# MIDILOOP_Schematic.net
KiCad netlist of a schematic drawn in EAGLE
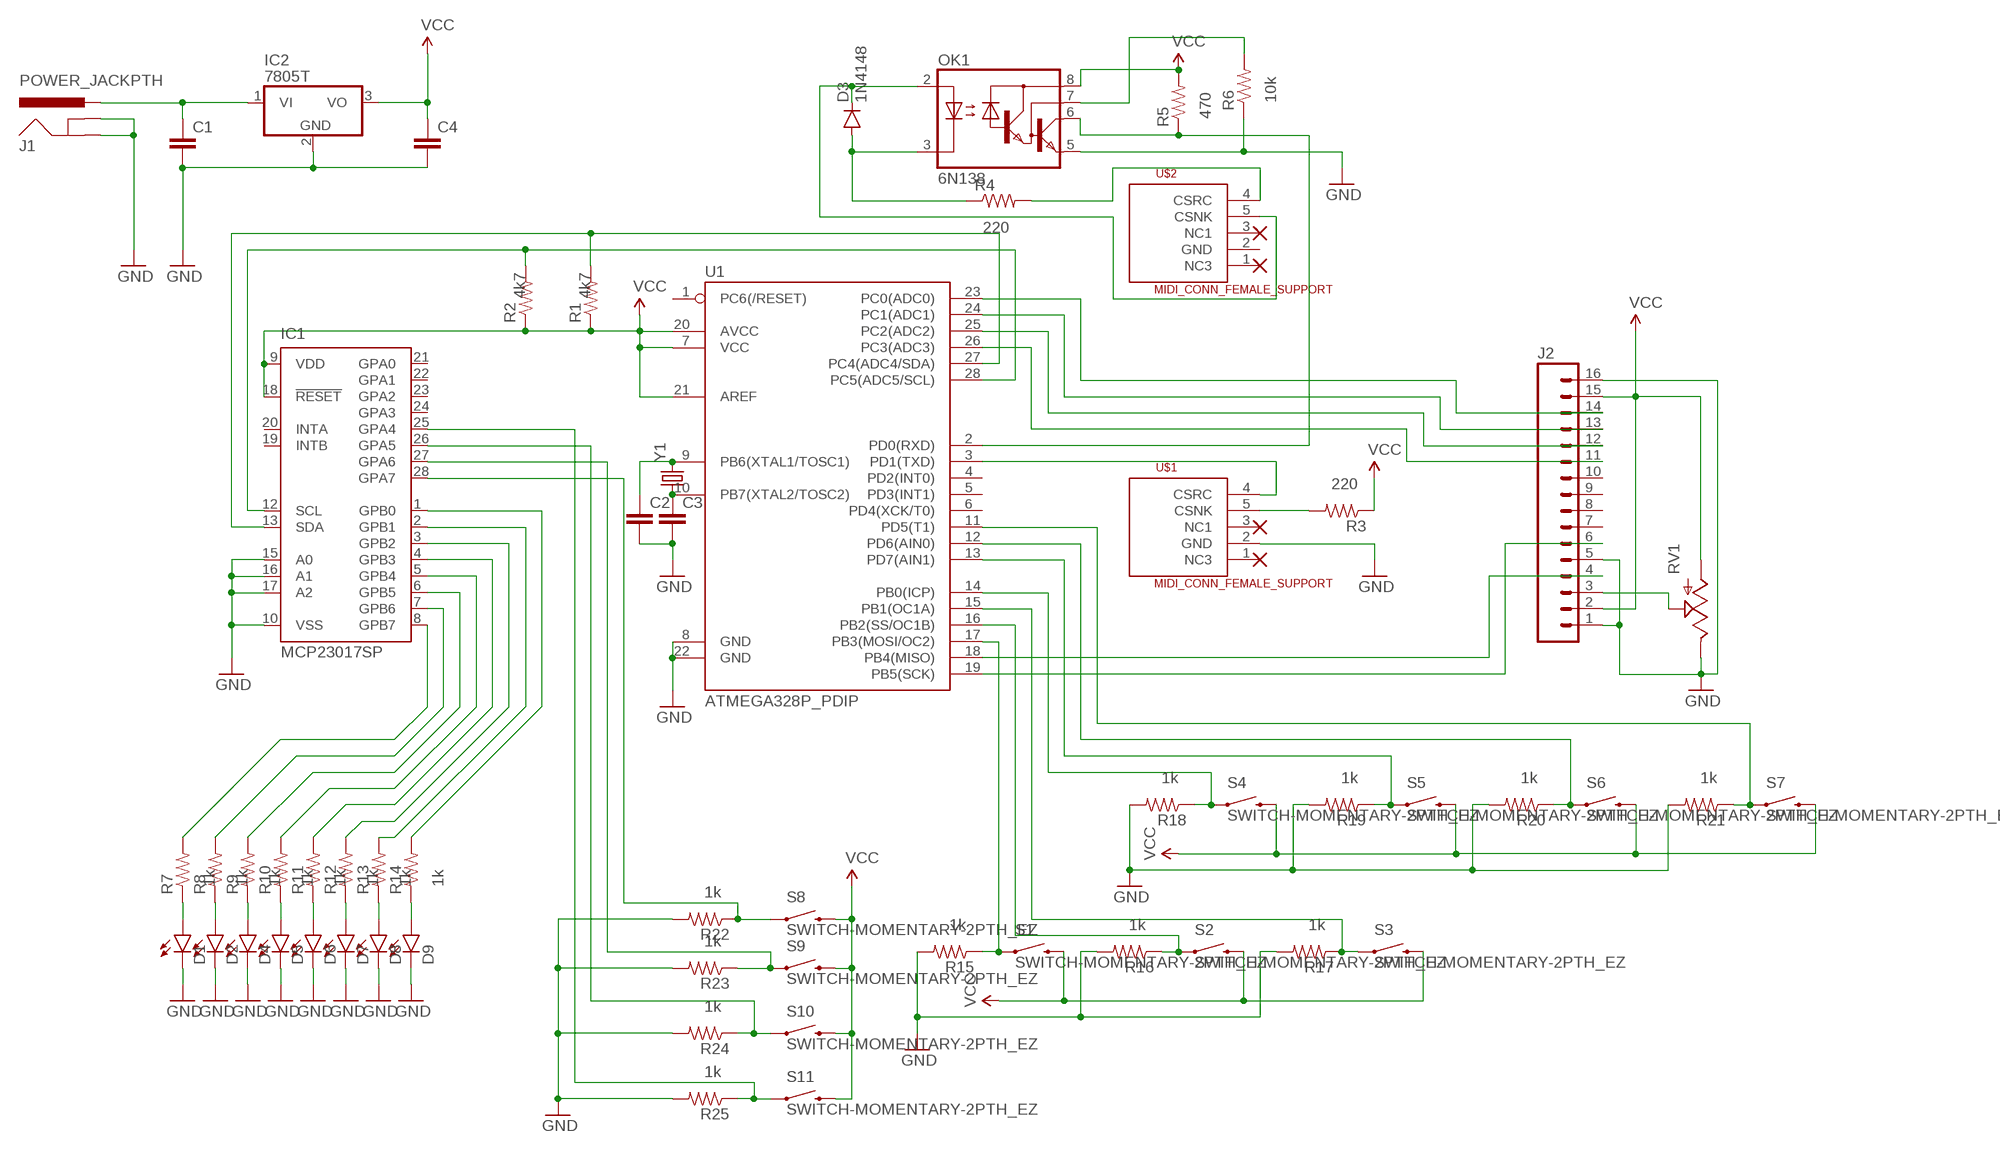
[diagram p0: schematic, sheet 1]

(export (version "E")
  (design (tool "Eeschema 10.0.6"))
  (components
    (comp (ref "C1")
      (value "CAPPTH1")
      (footprint "eagle-import:CAP-PTH-5MM")
      (libsource (lib "eagle-import") (part "SparkFun-Passives_CAPPTH1"))
    )
    (comp (ref "C2")
      (value "CAPPTH")
      (footprint "eagle-import:CAP-PTH-SMALL")
      (libsource (lib "eagle-import") (part "CAPPTH"))
    )
    (comp (ref "C3")
      (value "CAPPTH")
      (footprint "eagle-import:CAP-PTH-SMALL")
      (libsource (lib "eagle-import") (part "CAPPTH"))
    )
    (comp (ref "C4")
      (value "CAPPTH1")
      (footprint "eagle-import:CAP-PTH-5MM")
      (libsource (lib "eagle-import") (part "SparkFun-Passives_CAPPTH1"))
    )
    (comp (ref "D1")
      (value "LED3MM")
      (footprint "eagle-import:LED3MM")
      (libsource (lib "eagle-import") (part "LED3MM"))
    )
    (comp (ref "D2")
      (value "LED3MM")
      (footprint "eagle-import:LED3MM")
      (libsource (lib "eagle-import") (part "LED3MM"))
    )
    (comp (ref "D3")
      (value "1N4148")
      (footprint "eagle-import:DIODE-1N4148")
      (libsource (lib "eagle-import") (part "DIODE1N4148"))
    )
    (comp (ref "D4")
      (value "LED3MM")
      (footprint "eagle-import:LED3MM")
      (libsource (lib "eagle-import") (part "LED3MM"))
    )
    (comp (ref "D5")
      (value "LED3MM")
      (footprint "eagle-import:LED3MM")
      (libsource (lib "eagle-import") (part "LED3MM"))
    )
    (comp (ref "D6")
      (value "LED3MM")
      (footprint "eagle-import:LED3MM")
      (libsource (lib "eagle-import") (part "LED3MM"))
    )
    (comp (ref "D7")
      (value "LED3MM")
      (footprint "eagle-import:LED3MM")
      (libsource (lib "eagle-import") (part "LED3MM"))
    )
    (comp (ref "D8")
      (value "LED3MM")
      (footprint "eagle-import:LED3MM")
      (libsource (lib "eagle-import") (part "LED3MM"))
    )
    (comp (ref "D9")
      (value "LED3MM")
      (footprint "eagle-import:LED3MM")
      (libsource (lib "eagle-import") (part "LED3MM"))
    )
    (comp (ref "IC1")
      (value "MCP23017SP")
      (footprint "eagle-import:DIL28-3")
      (fields (field (name "MF") "MICROCHIP") (field (name "MPN") "MCP23017-E/SP"))
      (libsource (lib "eagle-import") (part "MCP23017SP"))
    )
    (comp (ref "IC2")
      (value "7805T")
      (footprint "eagle-import:TO220H")
      (libsource (lib "eagle-import") (part "78T05"))
    )
    (comp (ref "J1")
      (value "POWER_JACKPTH")
      (footprint "eagle-import:POWER_JACK_PTH")
      (libsource (lib "eagle-import") (part "POWER_JACKPTH"))
    )
    (comp (ref "J2")
      (value "M16LONGPADS")
      (footprint "eagle-import:1X16_LONGPADS")
      (libsource (lib "eagle-import") (part "M16LONGPADS"))
    )
    (comp (ref "OK1")
      (value "6N138")
      (footprint "eagle-import:DIL08")
      (fields (field (name "MF") "VISHAY/TELEFUNKEN"))
      (libsource (lib "eagle-import") (part "6N138"))
    )
    (comp (ref "R1")
      (value "RESISTOREZ")
      (footprint "eagle-import:AXIAL-0.3EZ")
      (fields (field (name "RESISTANCE") "4k7"))
      (libsource (lib "eagle-import") (part "RESISTOREZ"))
    )
    (comp (ref "R2")
      (value "RESISTOREZ")
      (footprint "eagle-import:AXIAL-0.3EZ")
      (fields (field (name "RESISTANCE") "4k7"))
      (libsource (lib "eagle-import") (part "RESISTOREZ"))
    )
    (comp (ref "R3")
      (value "RESISTOREZ")
      (footprint "eagle-import:AXIAL-0.3EZ")
      (fields (field (name "RESISTANCE") "220"))
      (libsource (lib "eagle-import") (part "RESISTOREZ"))
    )
    (comp (ref "R4")
      (value "RESISTOREZ")
      (footprint "eagle-import:AXIAL-0.3EZ")
      (fields (field (name "RESISTANCE") "220"))
      (libsource (lib "eagle-import") (part "RESISTOREZ"))
    )
    (comp (ref "R5")
      (value "RESISTOREZ")
      (footprint "eagle-import:AXIAL-0.3EZ")
      (fields (field (name "RESISTANCE") "470"))
      (libsource (lib "eagle-import") (part "RESISTOREZ"))
    )
    (comp (ref "R6")
      (value "RESISTOREZ")
      (footprint "eagle-import:AXIAL-0.3EZ")
      (fields (field (name "RESISTANCE") "10k"))
      (libsource (lib "eagle-import") (part "RESISTOREZ"))
    )
    (comp (ref "R7")
      (value "RESISTOREZ")
      (footprint "eagle-import:AXIAL-0.3EZ")
      (fields (field (name "RESISTANCE") "1k"))
      (libsource (lib "eagle-import") (part "RESISTOREZ"))
    )
    (comp (ref "R8")
      (value "RESISTOREZ")
      (footprint "eagle-import:AXIAL-0.3EZ")
      (fields (field (name "RESISTANCE") "1k"))
      (libsource (lib "eagle-import") (part "RESISTOREZ"))
    )
    (comp (ref "R9")
      (value "RESISTOREZ")
      (footprint "eagle-import:AXIAL-0.3EZ")
      (fields (field (name "RESISTANCE") "1k"))
      (libsource (lib "eagle-import") (part "RESISTOREZ"))
    )
    (comp (ref "R10")
      (value "RESISTOREZ")
      (footprint "eagle-import:AXIAL-0.3EZ")
      (fields (field (name "RESISTANCE") "1k"))
      (libsource (lib "eagle-import") (part "RESISTOREZ"))
    )
    (comp (ref "R11")
      (value "RESISTOREZ")
      (footprint "eagle-import:AXIAL-0.3EZ")
      (fields (field (name "RESISTANCE") "1k"))
      (libsource (lib "eagle-import") (part "RESISTOREZ"))
    )
    (comp (ref "R12")
      (value "RESISTOREZ")
      (footprint "eagle-import:AXIAL-0.3EZ")
      (fields (field (name "RESISTANCE") "1k"))
      (libsource (lib "eagle-import") (part "RESISTOREZ"))
    )
    (comp (ref "R13")
      (value "RESISTOREZ")
      (footprint "eagle-import:AXIAL-0.3EZ")
      (fields (field (name "RESISTANCE") "1k"))
      (libsource (lib "eagle-import") (part "RESISTOREZ"))
    )
    (comp (ref "R14")
      (value "RESISTOREZ")
      (footprint "eagle-import:AXIAL-0.3EZ")
      (fields (field (name "RESISTANCE") "1k"))
      (libsource (lib "eagle-import") (part "RESISTOREZ"))
    )
    (comp (ref "R15")
      (value "RESISTOREZ")
      (footprint "eagle-import:AXIAL-0.3EZ")
      (fields (field (name "RESISTANCE") "1k"))
      (libsource (lib "eagle-import") (part "RESISTOREZ"))
    )
    (comp (ref "R16")
      (value "RESISTOREZ")
      (footprint "eagle-import:AXIAL-0.3EZ")
      (fields (field (name "RESISTANCE") "1k"))
      (libsource (lib "eagle-import") (part "RESISTOREZ"))
    )
    (comp (ref "R17")
      (value "RESISTOREZ")
      (footprint "eagle-import:AXIAL-0.3EZ")
      (fields (field (name "RESISTANCE") "1k"))
      (libsource (lib "eagle-import") (part "RESISTOREZ"))
    )
    (comp (ref "R18")
      (value "RESISTOREZ")
      (footprint "eagle-import:AXIAL-0.3EZ")
      (fields (field (name "RESISTANCE") "1k"))
      (libsource (lib "eagle-import") (part "RESISTOREZ"))
    )
    (comp (ref "R19")
      (value "RESISTOREZ")
      (footprint "eagle-import:AXIAL-0.3EZ")
      (fields (field (name "RESISTANCE") "1k"))
      (libsource (lib "eagle-import") (part "RESISTOREZ"))
    )
    (comp (ref "R20")
      (value "RESISTOREZ")
      (footprint "eagle-import:AXIAL-0.3EZ")
      (fields (field (name "RESISTANCE") "1k"))
      (libsource (lib "eagle-import") (part "RESISTOREZ"))
    )
    (comp (ref "R21")
      (value "RESISTOREZ")
      (footprint "eagle-import:AXIAL-0.3EZ")
      (fields (field (name "RESISTANCE") "1k"))
      (libsource (lib "eagle-import") (part "RESISTOREZ"))
    )
    (comp (ref "R22")
      (value "RESISTOREZ")
      (footprint "eagle-import:AXIAL-0.3EZ")
      (fields (field (name "RESISTANCE") "1k"))
      (libsource (lib "eagle-import") (part "RESISTOREZ"))
    )
    (comp (ref "R23")
      (value "RESISTOREZ")
      (footprint "eagle-import:AXIAL-0.3EZ")
      (fields (field (name "RESISTANCE") "1k"))
      (libsource (lib "eagle-import") (part "RESISTOREZ"))
    )
    (comp (ref "R24")
      (value "RESISTOREZ")
      (footprint "eagle-import:AXIAL-0.3EZ")
      (fields (field (name "RESISTANCE") "1k"))
      (libsource (lib "eagle-import") (part "RESISTOREZ"))
    )
    (comp (ref "R25")
      (value "RESISTOREZ")
      (footprint "eagle-import:AXIAL-0.3EZ")
      (fields (field (name "RESISTANCE") "1k"))
      (libsource (lib "eagle-import") (part "RESISTOREZ"))
    )
    (comp (ref "RV1")
      (value "POTTRIM")
      (footprint "eagle-import:TRIM_POT")
      (libsource (lib "eagle-import") (part "POTTRIM"))
    )
    (comp (ref "S1")
      (value "SWITCH-MOMENTARY-2PTH_EZ")
      (footprint "eagle-import:TACTILE-PTH-EZ")
      (libsource (lib "eagle-import") (part "SWITCH-MOMENTARY-2PTH_EZ"))
    )
    (comp (ref "S2")
      (value "SWITCH-MOMENTARY-2PTH_EZ")
      (footprint "eagle-import:TACTILE-PTH-EZ")
      (libsource (lib "eagle-import") (part "SWITCH-MOMENTARY-2PTH_EZ"))
    )
    (comp (ref "S3")
      (value "SWITCH-MOMENTARY-2PTH_EZ")
      (footprint "eagle-import:TACTILE-PTH-EZ")
      (libsource (lib "eagle-import") (part "SWITCH-MOMENTARY-2PTH_EZ"))
    )
    (comp (ref "S4")
      (value "SWITCH-MOMENTARY-2PTH_EZ")
      (footprint "eagle-import:TACTILE-PTH-EZ")
      (libsource (lib "eagle-import") (part "SWITCH-MOMENTARY-2PTH_EZ"))
    )
    (comp (ref "S5")
      (value "SWITCH-MOMENTARY-2PTH_EZ")
      (footprint "eagle-import:TACTILE-PTH-EZ")
      (libsource (lib "eagle-import") (part "SWITCH-MOMENTARY-2PTH_EZ"))
    )
    (comp (ref "S6")
      (value "SWITCH-MOMENTARY-2PTH_EZ")
      (footprint "eagle-import:TACTILE-PTH-EZ")
      (libsource (lib "eagle-import") (part "SWITCH-MOMENTARY-2PTH_EZ"))
    )
    (comp (ref "S7")
      (value "SWITCH-MOMENTARY-2PTH_EZ")
      (footprint "eagle-import:TACTILE-PTH-EZ")
      (libsource (lib "eagle-import") (part "SWITCH-MOMENTARY-2PTH_EZ"))
    )
    (comp (ref "S8")
      (value "SWITCH-MOMENTARY-2PTH_EZ")
      (footprint "eagle-import:TACTILE-PTH-EZ")
      (libsource (lib "eagle-import") (part "SWITCH-MOMENTARY-2PTH_EZ"))
    )
    (comp (ref "S9")
      (value "SWITCH-MOMENTARY-2PTH_EZ")
      (footprint "eagle-import:TACTILE-PTH-EZ")
      (libsource (lib "eagle-import") (part "SWITCH-MOMENTARY-2PTH_EZ"))
    )
    (comp (ref "S10")
      (value "SWITCH-MOMENTARY-2PTH_EZ")
      (footprint "eagle-import:TACTILE-PTH-EZ")
      (libsource (lib "eagle-import") (part "SWITCH-MOMENTARY-2PTH_EZ"))
    )
    (comp (ref "S11")
      (value "SWITCH-MOMENTARY-2PTH_EZ")
      (footprint "eagle-import:TACTILE-PTH-EZ")
      (libsource (lib "eagle-import") (part "SWITCH-MOMENTARY-2PTH_EZ"))
    )
    (comp (ref "U$1")
      (value "MIDI_CONN_FEMALE_SUPPORT")
      (footprint "eagle-import:DIN_5_FEMALE_SUPPORT")
      (libsource (lib "eagle-import") (part "MIDI_CONN_FEMALE_SUPPORT"))
    )
    (comp (ref "U$2")
      (value "MIDI_CONN_FEMALE_SUPPORT")
      (footprint "eagle-import:DIN_5_FEMALE_SUPPORT")
      (libsource (lib "eagle-import") (part "MIDI_CONN_FEMALE_SUPPORT"))
    )
    (comp (ref "U1")
      (value "ATMEGA328P_PDIP")
      (footprint "eagle-import:DIL28-3")
      (libsource (lib "eagle-import") (part "ATMEGA328P_PDIP"))
    )
    (comp (ref "Y1")
      (value "CRYSTALHC49US")
      (footprint "eagle-import:HC49US")
      (libsource (lib "eagle-import") (part "CRYSTALHC49US"))
    )
  )
  (nets
    (net (code "1") (name "GND") (class "Default")
      (node (ref "C1") (pin "2") (pinfunction "2_2") (pintype "passive"))
      (node (ref "C2") (pin "2") (pinfunction "2_2") (pintype "passive"))
      (node (ref "C3") (pin "2") (pinfunction "2_2") (pintype "passive"))
      (node (ref "C4") (pin "2") (pinfunction "2_2") (pintype "passive"))
      (node (ref "D1") (pin "K") (pinfunction "C_K") (pintype "passive"))
      (node (ref "D2") (pin "K") (pinfunction "C_K") (pintype "passive"))
      (node (ref "D4") (pin "K") (pinfunction "C_K") (pintype "passive"))
      (node (ref "D5") (pin "K") (pinfunction "C_K") (pintype "passive"))
      (node (ref "D6") (pin "K") (pinfunction "C_K") (pintype "passive"))
      (node (ref "D7") (pin "K") (pinfunction "C_K") (pintype "passive"))
      (node (ref "D8") (pin "K") (pinfunction "C_K") (pintype "passive"))
      (node (ref "D9") (pin "K") (pinfunction "C_K") (pintype "passive"))
      (node (ref "IC1") (pin "10") (pinfunction "VSS_10") (pintype "power_in"))
      (node (ref "IC1") (pin "15") (pinfunction "A0_15") (pintype "input"))
      (node (ref "IC1") (pin "16") (pinfunction "A1_16") (pintype "input"))
      (node (ref "IC1") (pin "17") (pinfunction "A2_17") (pintype "input"))
      (node (ref "IC2") (pin "2") (pinfunction "GND_2") (pintype "passive"))
      (node (ref "J1") (pin "GND") (pinfunction "GND_GND") (pintype "bidirectional"))
      (node (ref "J1") (pin "GNDBREAK") (pinfunction "GNDBREAK_GNDBREAK") (pintype "bidirectional"))
      (node (ref "J2") (pin "1") (pinfunction "1_1") (pintype "passive"))
      (node (ref "J2") (pin "16") (pinfunction "16_16") (pintype "passive"))
      (node (ref "J2") (pin "5") (pinfunction "5_5") (pintype "passive"))
      (node (ref "OK1") (pin "5") (pinfunction "GND_5") (pintype "passive"))
      (node (ref "R15") (pin "P$2") (pinfunction "2_P$2") (pintype "passive"))
      (node (ref "R16") (pin "P$2") (pinfunction "2_P$2") (pintype "passive"))
      (node (ref "R17") (pin "P$2") (pinfunction "2_P$2") (pintype "passive"))
      (node (ref "R18") (pin "P$2") (pinfunction "2_P$2") (pintype "passive"))
      (node (ref "R19") (pin "P$2") (pinfunction "2_P$2") (pintype "passive"))
      (node (ref "R20") (pin "P$2") (pinfunction "2_P$2") (pintype "passive"))
      (node (ref "R21") (pin "P$2") (pinfunction "2_P$2") (pintype "passive"))
      (node (ref "R22") (pin "P$2") (pinfunction "2_P$2") (pintype "passive"))
      (node (ref "R23") (pin "P$2") (pinfunction "2_P$2") (pintype "passive"))
      (node (ref "R24") (pin "P$2") (pinfunction "2_P$2") (pintype "passive"))
      (node (ref "R25") (pin "P$2") (pinfunction "2_P$2") (pintype "passive"))
      (node (ref "R6") (pin "P$1") (pinfunction "1_P$1") (pintype "passive"))
      (node (ref "RV1") (pin "2") (pinfunction "E_2") (pintype "passive"))
      (node (ref "U$1") (pin "2") (pinfunction "GND_2") (pintype "bidirectional"))
      (node (ref "U1") (pin "22") (pinfunction "GND_22") (pintype "bidirectional"))
      (node (ref "U1") (pin "8") (pinfunction "GND_8") (pintype "bidirectional"))
    )
    (net (code "2") (name "Net-(IC1-GPA4)") (class "Default")
      (node (ref "IC1") (pin "25") (pinfunction "GPA4_25") (pintype "bidirectional"))
      (node (ref "R25") (pin "P$1") (pinfunction "1_P$1") (pintype "passive"))
      (node (ref "S11") (pin "1") (pinfunction "1_1") (pintype "passive"))
    )
    (net (code "3") (name "Net-(IC1-GPA5)") (class "Default")
      (node (ref "IC1") (pin "26") (pinfunction "GPA5_26") (pintype "bidirectional"))
      (node (ref "R24") (pin "P$1") (pinfunction "1_P$1") (pintype "passive"))
      (node (ref "S10") (pin "1") (pinfunction "1_1") (pintype "passive"))
    )
    (net (code "4") (name "Net-(IC1-GPA6)") (class "Default")
      (node (ref "IC1") (pin "27") (pinfunction "GPA6_27") (pintype "bidirectional"))
      (node (ref "R23") (pin "P$1") (pinfunction "1_P$1") (pintype "passive"))
      (node (ref "S9") (pin "1") (pinfunction "1_1") (pintype "passive"))
    )
    (net (code "5") (name "Net-(IC1-GPA7)") (class "Default")
      (node (ref "IC1") (pin "28") (pinfunction "GPA7_28") (pintype "bidirectional"))
      (node (ref "R22") (pin "P$1") (pinfunction "1_P$1") (pintype "passive"))
      (node (ref "S8") (pin "1") (pinfunction "1_1") (pintype "passive"))
    )
    (net (code "6") (name "Net-(IC1-GPB0)") (class "Default")
      (node (ref "IC1") (pin "1") (pinfunction "GPB0_1") (pintype "bidirectional"))
      (node (ref "R14") (pin "P$2") (pinfunction "2_P$2") (pintype "passive"))
    )
    (net (code "7") (name "Net-(IC1-GPB1)") (class "Default")
      (node (ref "IC1") (pin "2") (pinfunction "GPB1_2") (pintype "bidirectional"))
      (node (ref "R13") (pin "P$2") (pinfunction "2_P$2") (pintype "passive"))
    )
    (net (code "8") (name "Net-(IC1-GPB2)") (class "Default")
      (node (ref "IC1") (pin "3") (pinfunction "GPB2_3") (pintype "bidirectional"))
      (node (ref "R12") (pin "P$2") (pinfunction "2_P$2") (pintype "passive"))
    )
    (net (code "9") (name "Net-(IC1-GPB3)") (class "Default")
      (node (ref "IC1") (pin "4") (pinfunction "GPB3_4") (pintype "bidirectional"))
      (node (ref "R11") (pin "P$2") (pinfunction "2_P$2") (pintype "passive"))
    )
    (net (code "10") (name "Net-(IC1-GPB4)") (class "Default")
      (node (ref "IC1") (pin "5") (pinfunction "GPB4_5") (pintype "bidirectional"))
      (node (ref "R10") (pin "P$2") (pinfunction "2_P$2") (pintype "passive"))
    )
    (net (code "11") (name "Net-(IC1-GPB5)") (class "Default")
      (node (ref "IC1") (pin "6") (pinfunction "GPB5_6") (pintype "bidirectional"))
      (node (ref "R9") (pin "P$2") (pinfunction "2_P$2") (pintype "passive"))
    )
    (net (code "12") (name "Net-(IC1-GPB6)") (class "Default")
      (node (ref "IC1") (pin "7") (pinfunction "GPB6_7") (pintype "bidirectional"))
      (node (ref "R8") (pin "P$2") (pinfunction "2_P$2") (pintype "passive"))
    )
    (net (code "13") (name "Net-(IC1-GPB7)") (class "Default")
      (node (ref "IC1") (pin "8") (pinfunction "GPB7_8") (pintype "bidirectional"))
      (node (ref "R7") (pin "P$2") (pinfunction "2_P$2") (pintype "passive"))
    )
    (net (code "14") (name "Net-(IC1-SCL)") (class "Default")
      (node (ref "IC1") (pin "12") (pinfunction "SCL_12") (pintype "input"))
      (node (ref "R2") (pin "P$2") (pinfunction "2_P$2") (pintype "passive"))
      (node (ref "U1") (pin "28") (pinfunction "PC5(ADC5/SCL)_28") (pintype "bidirectional"))
    )
    (net (code "15") (name "Net-(IC1-SDA)") (class "Default")
      (node (ref "IC1") (pin "13") (pinfunction "SDA_13") (pintype "bidirectional"))
      (node (ref "R1") (pin "P$2") (pinfunction "2_P$2") (pintype "passive"))
      (node (ref "U1") (pin "27") (pinfunction "PC4(ADC4/SDA)_27") (pintype "bidirectional"))
    )
    (net (code "16") (name "Net-(IC2-VI)") (class "Default")
      (node (ref "C1") (pin "1") (pinfunction "1_1") (pintype "passive"))
      (node (ref "IC2") (pin "1") (pinfunction "VI_1") (pintype "input"))
      (node (ref "J1") (pin "PWR") (pinfunction "PWR_PWR") (pintype "bidirectional"))
    )
    (net (code "17") (name "Net-(OK1-A)") (class "Default")
      (node (ref "D3") (pin "C") (pinfunction "C_C") (pintype "passive"))
      (node (ref "OK1") (pin "2") (pinfunction "A_2") (pintype "passive"))
      (node (ref "U$2") (pin "5") (pinfunction "CSNK_5") (pintype "bidirectional"))
    )
    (net (code "18") (name "Net-(OK1-C)") (class "Default")
      (node (ref "D3") (pin "A") (pinfunction "A_A") (pintype "passive"))
      (node (ref "OK1") (pin "3") (pinfunction "C_3") (pintype "passive"))
      (node (ref "R4") (pin "P$1") (pinfunction "1_P$1") (pintype "passive"))
    )
    (net (code "19") (name "Net-(OK1-VB)") (class "Default")
      (node (ref "OK1") (pin "7") (pinfunction "VB_7") (pintype "passive"))
      (node (ref "R6") (pin "P$2") (pinfunction "2_P$2") (pintype "passive"))
    )
    (net (code "20") (name "Net-(OK1-VO)") (class "Default")
      (node (ref "OK1") (pin "6") (pinfunction "VO_6") (pintype "passive"))
      (node (ref "R5") (pin "P$1") (pinfunction "1_P$1") (pintype "passive"))
      (node (ref "U1") (pin "2") (pinfunction "PD0(RXD)_2") (pintype "bidirectional"))
    )
    (net (code "21") (name "Net-(R3-2)") (class "Default")
      (node (ref "R3") (pin "P$2") (pinfunction "2_P$2") (pintype "passive"))
      (node (ref "U$1") (pin "5") (pinfunction "CSNK_5") (pintype "bidirectional"))
    )
    (net (code "22") (name "Net-(R4-2)") (class "Default")
      (node (ref "R4") (pin "P$2") (pinfunction "2_P$2") (pintype "passive"))
      (node (ref "U$2") (pin "4") (pinfunction "CSRC_4") (pintype "bidirectional"))
    )
    (net (code "23") (name "Net-(R7-1)") (class "Default")
      (node (ref "D1") (pin "A") (pinfunction "A_A") (pintype "passive"))
      (node (ref "R7") (pin "P$1") (pinfunction "1_P$1") (pintype "passive"))
    )
    (net (code "24") (name "Net-(R8-1)") (class "Default")
      (node (ref "D2") (pin "A") (pinfunction "A_A") (pintype "passive"))
      (node (ref "R8") (pin "P$1") (pinfunction "1_P$1") (pintype "passive"))
    )
    (net (code "25") (name "Net-(R9-1)") (class "Default")
      (node (ref "D4") (pin "A") (pinfunction "A_A") (pintype "passive"))
      (node (ref "R9") (pin "P$1") (pinfunction "1_P$1") (pintype "passive"))
    )
    (net (code "26") (name "Net-(R10-1)") (class "Default")
      (node (ref "D5") (pin "A") (pinfunction "A_A") (pintype "passive"))
      (node (ref "R10") (pin "P$1") (pinfunction "1_P$1") (pintype "passive"))
    )
    (net (code "27") (name "Net-(R11-1)") (class "Default")
      (node (ref "D6") (pin "A") (pinfunction "A_A") (pintype "passive"))
      (node (ref "R11") (pin "P$1") (pinfunction "1_P$1") (pintype "passive"))
    )
    (net (code "28") (name "Net-(R12-1)") (class "Default")
      (node (ref "D7") (pin "A") (pinfunction "A_A") (pintype "passive"))
      (node (ref "R12") (pin "P$1") (pinfunction "1_P$1") (pintype "passive"))
    )
    (net (code "29") (name "Net-(R13-1)") (class "Default")
      (node (ref "D8") (pin "A") (pinfunction "A_A") (pintype "passive"))
      (node (ref "R13") (pin "P$1") (pinfunction "1_P$1") (pintype "passive"))
    )
    (net (code "30") (name "Net-(R14-1)") (class "Default")
      (node (ref "D9") (pin "A") (pinfunction "A_A") (pintype "passive"))
      (node (ref "R14") (pin "P$1") (pinfunction "1_P$1") (pintype "passive"))
    )
    (net (code "31") (name "Net-(R15-1)") (class "Default")
      (node (ref "R15") (pin "P$1") (pinfunction "1_P$1") (pintype "passive"))
      (node (ref "S1") (pin "1") (pinfunction "1_1") (pintype "passive"))
      (node (ref "U1") (pin "17") (pinfunction "PB3(MOSI/OC2)_17") (pintype "bidirectional"))
    )
    (net (code "32") (name "Net-(R16-1)") (class "Default")
      (node (ref "R16") (pin "P$1") (pinfunction "1_P$1") (pintype "passive"))
      (node (ref "S2") (pin "1") (pinfunction "1_1") (pintype "passive"))
      (node (ref "U1") (pin "16") (pinfunction "PB2(SS/OC1B)_16") (pintype "bidirectional"))
    )
    (net (code "33") (name "Net-(R17-1)") (class "Default")
      (node (ref "R17") (pin "P$1") (pinfunction "1_P$1") (pintype "passive"))
      (node (ref "S3") (pin "1") (pinfunction "1_1") (pintype "passive"))
      (node (ref "U1") (pin "15") (pinfunction "PB1(OC1A)_15") (pintype "bidirectional"))
    )
    (net (code "34") (name "Net-(R18-1)") (class "Default")
      (node (ref "R18") (pin "P$1") (pinfunction "1_P$1") (pintype "passive"))
      (node (ref "S4") (pin "1") (pinfunction "1_1") (pintype "passive"))
      (node (ref "U1") (pin "14") (pinfunction "PB0(ICP)_14") (pintype "bidirectional"))
    )
    (net (code "35") (name "Net-(R19-1)") (class "Default")
      (node (ref "R19") (pin "P$1") (pinfunction "1_P$1") (pintype "passive"))
      (node (ref "S5") (pin "1") (pinfunction "1_1") (pintype "passive"))
      (node (ref "U1") (pin "13") (pinfunction "PD7(AIN1)_13") (pintype "bidirectional"))
    )
    (net (code "36") (name "Net-(R20-1)") (class "Default")
      (node (ref "R20") (pin "P$1") (pinfunction "1_P$1") (pintype "passive"))
      (node (ref "S6") (pin "1") (pinfunction "1_1") (pintype "passive"))
      (node (ref "U1") (pin "12") (pinfunction "PD6(AIN0)_12") (pintype "bidirectional"))
    )
    (net (code "37") (name "Net-(R21-1)") (class "Default")
      (node (ref "R21") (pin "P$1") (pinfunction "1_P$1") (pintype "passive"))
      (node (ref "S7") (pin "1") (pinfunction "1_1") (pintype "passive"))
      (node (ref "U1") (pin "11") (pinfunction "PD5(T1)_11") (pintype "bidirectional"))
    )
    (net (code "38") (name "Net-(RV1-S)") (class "Default")
      (node (ref "J2") (pin "3") (pinfunction "3_3") (pintype "passive"))
      (node (ref "RV1") (pin "1") (pinfunction "S_1") (pintype "passive"))
    )
    (net (code "39") (name "Net-(U$1-CSRC)") (class "Default")
      (node (ref "U$1") (pin "4") (pinfunction "CSRC_4") (pintype "bidirectional"))
      (node (ref "U1") (pin "3") (pinfunction "PD1(TXD)_3") (pintype "bidirectional"))
    )
    (net (code "40") (name "Net-(U1-PB4(MISO))") (class "Default")
      (node (ref "J2") (pin "4") (pinfunction "4_4") (pintype "passive"))
      (node (ref "U1") (pin "18") (pinfunction "PB4(MISO)_18") (pintype "bidirectional"))
    )
    (net (code "41") (name "Net-(U1-PB5(SCK))") (class "Default")
      (node (ref "J2") (pin "6") (pinfunction "6_6") (pintype "passive"))
      (node (ref "U1") (pin "19") (pinfunction "PB5(SCK)_19") (pintype "bidirectional"))
    )
    (net (code "42") (name "Net-(U1-PB6(XTAL1{slash}TOSC1))") (class "Default")
      (node (ref "C2") (pin "1") (pinfunction "1_1") (pintype "passive"))
      (node (ref "U1") (pin "9") (pinfunction "PB6(XTAL1/TOSC1)_9") (pintype "bidirectional"))
      (node (ref "Y1") (pin "2") (pinfunction "2_2") (pintype "passive"))
    )
    (net (code "43") (name "Net-(U1-PB7(XTAL2{slash}TOSC2))") (class "Default")
      (node (ref "C3") (pin "1") (pinfunction "1_1") (pintype "passive"))
      (node (ref "U1") (pin "10") (pinfunction "PB7(XTAL2/TOSC2)_10") (pintype "bidirectional"))
      (node (ref "Y1") (pin "1") (pinfunction "1_1") (pintype "passive"))
    )
    (net (code "44") (name "Net-(U1-PC0(ADC0))") (class "Default")
      (node (ref "J2") (pin "14") (pinfunction "14_14") (pintype "passive"))
      (node (ref "U1") (pin "23") (pinfunction "PC0(ADC0)_23") (pintype "bidirectional"))
    )
    (net (code "45") (name "Net-(U1-PC1(ADC1))") (class "Default")
      (node (ref "J2") (pin "13") (pinfunction "13_13") (pintype "passive"))
      (node (ref "U1") (pin "24") (pinfunction "PC1(ADC1)_24") (pintype "bidirectional"))
    )
    (net (code "46") (name "Net-(U1-PC2(ADC2))") (class "Default")
      (node (ref "J2") (pin "12") (pinfunction "12_12") (pintype "passive"))
      (node (ref "U1") (pin "25") (pinfunction "PC2(ADC2)_25") (pintype "bidirectional"))
    )
    (net (code "47") (name "Net-(U1-PC3(ADC3))") (class "Default")
      (node (ref "J2") (pin "11") (pinfunction "11_11") (pintype "passive"))
      (node (ref "U1") (pin "26") (pinfunction "PC3(ADC3)_26") (pintype "bidirectional"))
    )
    (net (code "48") (name "VCC") (class "Default")
      (node (ref "C4") (pin "1") (pinfunction "1_1") (pintype "passive"))
      (node (ref "IC1") (pin "18") (pinfunction "~{RESET}_18") (pintype "input"))
      (node (ref "IC1") (pin "9") (pinfunction "VDD_9") (pintype "power_in"))
      (node (ref "IC2") (pin "3") (pinfunction "VO_3") (pintype "passive"))
      (node (ref "J2") (pin "15") (pinfunction "15_15") (pintype "passive"))
      (node (ref "J2") (pin "2") (pinfunction "2_2") (pintype "passive"))
      (node (ref "OK1") (pin "8") (pinfunction "VCC_8") (pintype "passive"))
      (node (ref "R1") (pin "P$1") (pinfunction "1_P$1") (pintype "passive"))
      (node (ref "R2") (pin "P$1") (pinfunction "1_P$1") (pintype "passive"))
      (node (ref "R3") (pin "P$1") (pinfunction "1_P$1") (pintype "passive"))
      (node (ref "R5") (pin "P$2") (pinfunction "2_P$2") (pintype "passive"))
      (node (ref "RV1") (pin "3") (pinfunction "A_3") (pintype "passive"))
      (node (ref "S1") (pin "3") (pinfunction "2_3") (pintype "passive"))
      (node (ref "S10") (pin "3") (pinfunction "2_3") (pintype "passive"))
      (node (ref "S11") (pin "3") (pinfunction "2_3") (pintype "passive"))
      (node (ref "S2") (pin "3") (pinfunction "2_3") (pintype "passive"))
      (node (ref "S3") (pin "3") (pinfunction "2_3") (pintype "passive"))
      (node (ref "S4") (pin "3") (pinfunction "2_3") (pintype "passive"))
      (node (ref "S5") (pin "3") (pinfunction "2_3") (pintype "passive"))
      (node (ref "S6") (pin "3") (pinfunction "2_3") (pintype "passive"))
      (node (ref "S7") (pin "3") (pinfunction "2_3") (pintype "passive"))
      (node (ref "S8") (pin "3") (pinfunction "2_3") (pintype "passive"))
      (node (ref "S9") (pin "3") (pinfunction "2_3") (pintype "passive"))
      (node (ref "U1") (pin "20") (pinfunction "AVCC_20") (pintype "bidirectional"))
      (node (ref "U1") (pin "21") (pinfunction "AREF_21") (pintype "bidirectional"))
      (node (ref "U1") (pin "7") (pinfunction "VCC_7") (pintype "bidirectional"))
    )
    (net (code "49") (name "unconnected-(IC1-GPA0-Pad21)") (class "Default")
      (node (ref "IC1") (pin "21") (pinfunction "GPA0_21") (pintype "bidirectional"))
    )
    (net (code "50") (name "unconnected-(IC1-GPA1-Pad22)") (class "Default")
      (node (ref "IC1") (pin "22") (pinfunction "GPA1_22") (pintype "bidirectional"))
    )
    (net (code "51") (name "unconnected-(IC1-GPA2-Pad23)") (class "Default")
      (node (ref "IC1") (pin "23") (pinfunction "GPA2_23") (pintype "bidirectional"))
    )
    (net (code "52") (name "unconnected-(IC1-GPA3-Pad24)") (class "Default")
      (node (ref "IC1") (pin "24") (pinfunction "GPA3_24") (pintype "bidirectional"))
    )
    (net (code "53") (name "unconnected-(IC1-INTA-Pad20)") (class "Default")
      (node (ref "IC1") (pin "20") (pinfunction "INTA_20") (pintype "output"))
    )
    (net (code "54") (name "unconnected-(IC1-INTB-Pad19)") (class "Default")
      (node (ref "IC1") (pin "19") (pinfunction "INTB_19") (pintype "output"))
    )
    (net (code "55") (name "unconnected-(J2-Pad7)") (class "Default")
      (node (ref "J2") (pin "7") (pinfunction "7_7") (pintype "passive"))
    )
    (net (code "56") (name "unconnected-(J2-Pad8)") (class "Default")
      (node (ref "J2") (pin "8") (pinfunction "8_8") (pintype "passive"))
    )
    (net (code "57") (name "unconnected-(J2-Pad9)") (class "Default")
      (node (ref "J2") (pin "9") (pinfunction "9_9") (pintype "passive"))
    )
    (net (code "58") (name "unconnected-(J2-Pad10)") (class "Default")
      (node (ref "J2") (pin "10") (pinfunction "10_10") (pintype "passive"))
    )
    (net (code "59") (name "unconnected-(U$1-NC1-Pad3)") (class "Default")
      (node (ref "U$1") (pin "3") (pinfunction "NC1_3") (pintype "bidirectional"))
    )
    (net (code "60") (name "unconnected-(U$1-NC3-Pad1)") (class "Default")
      (node (ref "U$1") (pin "1") (pinfunction "NC3_1") (pintype "bidirectional"))
    )
    (net (code "61") (name "unconnected-(U$2-GND-Pad2)") (class "Default")
      (node (ref "U$2") (pin "2") (pinfunction "GND_2") (pintype "bidirectional"))
    )
    (net (code "62") (name "unconnected-(U$2-NC1-Pad3)") (class "Default")
      (node (ref "U$2") (pin "3") (pinfunction "NC1_3") (pintype "bidirectional"))
    )
    (net (code "63") (name "unconnected-(U$2-NC3-Pad1)") (class "Default")
      (node (ref "U$2") (pin "1") (pinfunction "NC3_1") (pintype "bidirectional"))
    )
    (net (code "64") (name "unconnected-(U1-PC6({slash}RESET)-Pad1)") (class "Default")
      (node (ref "U1") (pin "1") (pinfunction "PC6(/RESET)_1") (pintype "bidirectional"))
    )
    (net (code "65") (name "unconnected-(U1-PD2(INT0)-Pad4)") (class "Default")
      (node (ref "U1") (pin "4") (pinfunction "PD2(INT0)_4") (pintype "bidirectional"))
    )
    (net (code "66") (name "unconnected-(U1-PD3(INT1)-Pad5)") (class "Default")
      (node (ref "U1") (pin "5") (pinfunction "PD3(INT1)_5") (pintype "bidirectional"))
    )
    (net (code "67") (name "unconnected-(U1-PD4(XCK{slash}T0)-Pad6)") (class "Default")
      (node (ref "U1") (pin "6") (pinfunction "PD4(XCK/T0)_6") (pintype "bidirectional"))
    )
  )
)
